# Sumo_main.net
KiCad netlist of a schematic drawn in EAGLE
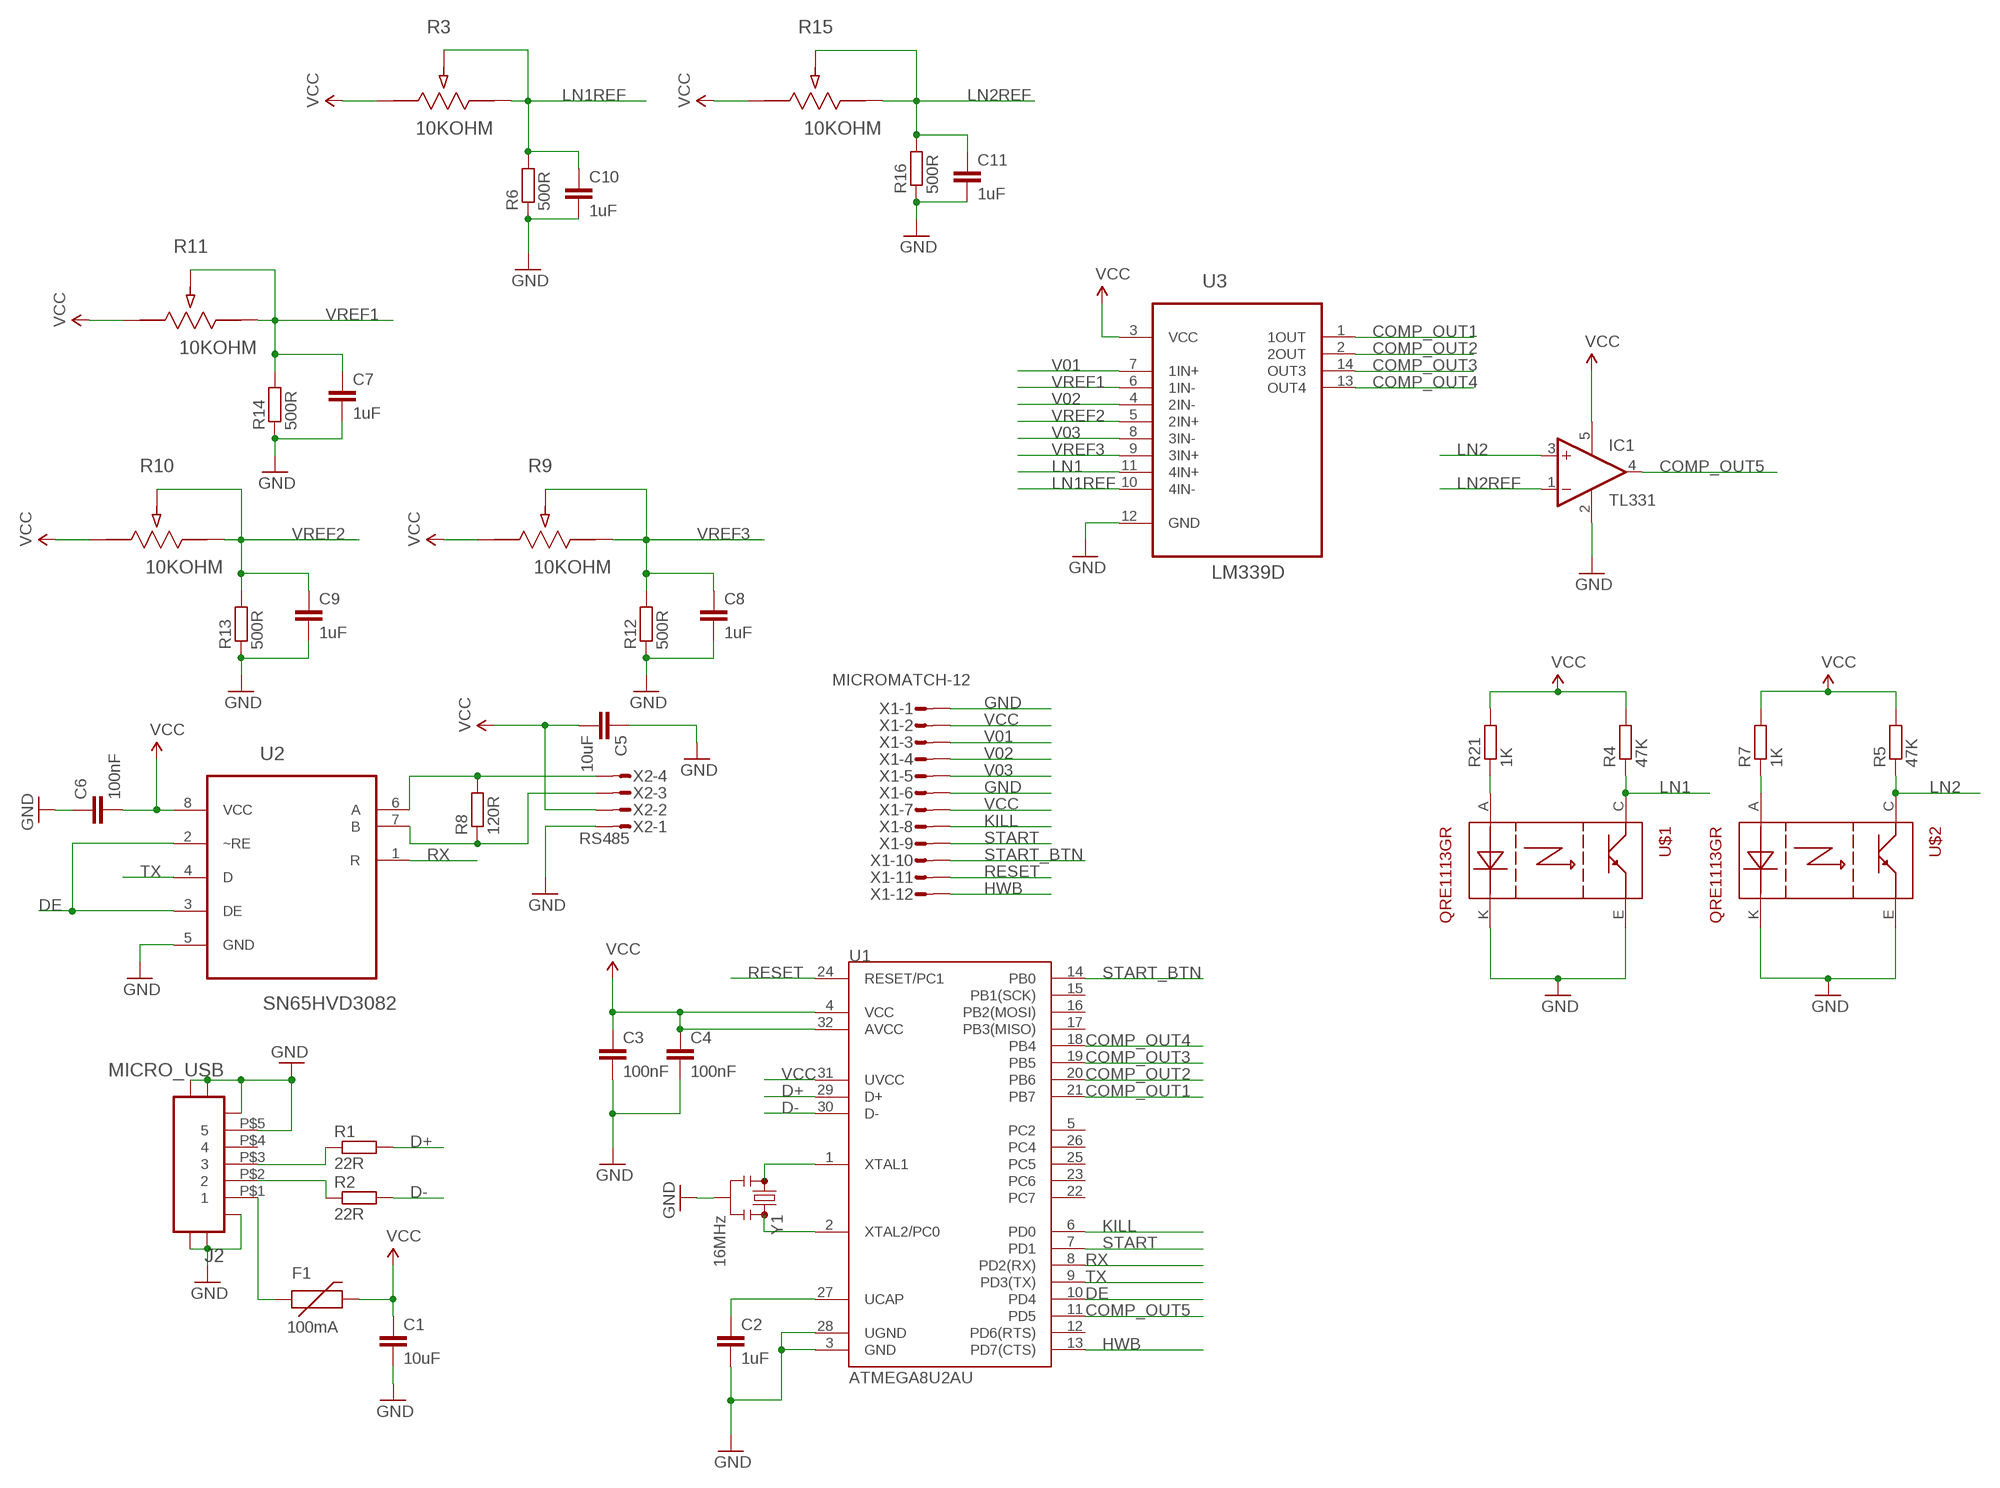
[diagram p0: schematic, sheet 1]

(export (version "E")
  (design (tool "Eeschema 10.0.6"))
  (components
    (comp (ref "C1")
      (value "10uF")
      (footprint "eagle-import:0603-CAP")
      (libsource (lib "eagle-import") (part "CAP0603-CAP"))
    )
    (comp (ref "C2")
      (value "1uF")
      (footprint "eagle-import:0603-CAP")
      (libsource (lib "eagle-import") (part "CAP0603-CAP"))
    )
    (comp (ref "C3")
      (value "100nF")
      (footprint "eagle-import:0603-CAP")
      (libsource (lib "eagle-import") (part "CAP0603-CAP"))
    )
    (comp (ref "C4")
      (value "100nF")
      (footprint "eagle-import:0603-CAP")
      (libsource (lib "eagle-import") (part "CAP0603-CAP"))
    )
    (comp (ref "C5")
      (value "10uF")
      (footprint "eagle-import:0603-CAP")
      (libsource (lib "eagle-import") (part "CAP0603-CAP"))
    )
    (comp (ref "C6")
      (value "100nF")
      (footprint "eagle-import:0603-CAP")
      (libsource (lib "eagle-import") (part "CAP0603-CAP"))
    )
    (comp (ref "C7")
      (value "1uF")
      (footprint "eagle-import:0603-CAP")
      (libsource (lib "eagle-import") (part "CAP0603-CAP"))
    )
    (comp (ref "C8")
      (value "1uF")
      (footprint "eagle-import:0603-CAP")
      (libsource (lib "eagle-import") (part "CAP0603-CAP"))
    )
    (comp (ref "C9")
      (value "1uF")
      (footprint "eagle-import:0603-CAP")
      (libsource (lib "eagle-import") (part "CAP0603-CAP"))
    )
    (comp (ref "C10")
      (value "1uF")
      (footprint "eagle-import:0603-CAP")
      (libsource (lib "eagle-import") (part "CAP0603-CAP"))
    )
    (comp (ref "C11")
      (value "1uF")
      (footprint "eagle-import:0603-CAP")
      (libsource (lib "eagle-import") (part "CAP0603-CAP"))
    )
    (comp (ref "F1")
      (value "100mA")
      (footprint "eagle-import:PTC-1206")
      (libsource (lib "eagle-import") (part "PTCSMD"))
    )
    (comp (ref "IC1")
      (value "TL331")
      (footprint "eagle-import:DBV-R-PDSO-G5")
      (libsource (lib "eagle-import") (part "TL331"))
    )
    (comp (ref "J2")
      (value "MICRO_USB")
      (footprint "eagle-import:MOLEX_47346-0001")
      (fields (field (name "MPN") "47346-0001"))
      (libsource (lib "eagle-import") (part "47346-0001"))
    )
    (comp (ref "R1")
      (value "22R")
      (footprint "eagle-import:R0603")
      (libsource (lib "eagle-import") (part "R-EU_R0603"))
    )
    (comp (ref "R2")
      (value "22R")
      (footprint "eagle-import:R0603")
      (libsource (lib "eagle-import") (part "R-EU_R0603"))
    )
    (comp (ref "R3")
      (value "10KOHM")
      (footprint "eagle-import:POT_EVM3W")
      (fields (field (name "MPN") "EVM3YSX50B14") (field (name "TOLERANCE") "±25 %"))
      (libsource (lib "eagle-import") (part "EVM-3W3YSX50B14"))
    )
    (comp (ref "R4")
      (value "47K")
      (footprint "eagle-import:R0603")
      (libsource (lib "eagle-import") (part "R-EU_R0603"))
    )
    (comp (ref "R5")
      (value "47K")
      (footprint "eagle-import:R0603")
      (libsource (lib "eagle-import") (part "R-EU_R0603"))
    )
    (comp (ref "R6")
      (value "500R")
      (footprint "eagle-import:R0603")
      (libsource (lib "eagle-import") (part "R-EU_R0603"))
    )
    (comp (ref "R7")
      (value "1K")
      (footprint "eagle-import:R0603")
      (libsource (lib "eagle-import") (part "R-EU_R0603"))
    )
    (comp (ref "R8")
      (value "120R")
      (footprint "eagle-import:R0603")
      (libsource (lib "eagle-import") (part "R-EU_R0603"))
    )
    (comp (ref "R9")
      (value "10KOHM")
      (footprint "eagle-import:POT_EVM3W")
      (fields (field (name "MPN") "EVM3YSX50B14") (field (name "TOLERANCE") "±25 %"))
      (libsource (lib "eagle-import") (part "EVM-3W3YSX50B14"))
    )
    (comp (ref "R10")
      (value "10KOHM")
      (footprint "eagle-import:POT_EVM3W")
      (fields (field (name "MPN") "EVM3YSX50B14") (field (name "TOLERANCE") "±25 %"))
      (libsource (lib "eagle-import") (part "EVM-3W3YSX50B14"))
    )
    (comp (ref "R11")
      (value "10KOHM")
      (footprint "eagle-import:POT_EVM3W")
      (fields (field (name "MPN") "EVM3YSX50B14") (field (name "TOLERANCE") "±25 %"))
      (libsource (lib "eagle-import") (part "EVM-3W3YSX50B14"))
    )
    (comp (ref "R12")
      (value "500R")
      (footprint "eagle-import:R0603")
      (libsource (lib "eagle-import") (part "R-EU_R0603"))
    )
    (comp (ref "R13")
      (value "500R")
      (footprint "eagle-import:R0603")
      (libsource (lib "eagle-import") (part "R-EU_R0603"))
    )
    (comp (ref "R14")
      (value "500R")
      (footprint "eagle-import:R0603")
      (libsource (lib "eagle-import") (part "R-EU_R0603"))
    )
    (comp (ref "R15")
      (value "10KOHM")
      (footprint "eagle-import:POT_EVM3W")
      (fields (field (name "MPN") "EVM3YSX50B14") (field (name "TOLERANCE") "±25 %"))
      (libsource (lib "eagle-import") (part "EVM-3W3YSX50B14"))
    )
    (comp (ref "R16")
      (value "500R")
      (footprint "eagle-import:R0603")
      (libsource (lib "eagle-import") (part "R-EU_R0603"))
    )
    (comp (ref "R21")
      (value "1K")
      (footprint "eagle-import:R0603")
      (libsource (lib "eagle-import") (part "R-EU_R0603"))
    )
    (comp (ref "U$1")
      (value "QRE1113GR")
      (footprint "eagle-import:4LEADSMD")
      (libsource (lib "eagle-import") (part "QRE1113GR"))
    )
    (comp (ref "U$2")
      (value "QRE1113GR")
      (footprint "eagle-import:4LEADSMD")
      (libsource (lib "eagle-import") (part "QRE1113GR"))
    )
    (comp (ref "U1")
      (value "ATMEGA8U2AU")
      (footprint "eagle-import:TQFP32-08")
      (libsource (lib "eagle-import") (part "ATMEGA8U2AU"))
    )
    (comp (ref "U2")
      (value "SN65HVD3082")
      (footprint "eagle-import:SOIC127P600X175-8N")
      (fields (field (name "MPN") "SN65HVD3082ED"))
      (libsource (lib "eagle-import") (part "SN65HVD3082ED"))
    )
    (comp (ref "U3")
      (value "LM339D")
      (footprint "eagle-import:SOIC127P600X175-14N")
      (libsource (lib "eagle-import") (part "LM339D"))
    )
    (comp (ref "X1")
      (value "MICROMATCH-12")
      (footprint "eagle-import:MICROMATCH-12")
      (fields (field (name "MF") "FARNELL") (field (name "MPN") "8-215464-2"))
      (libsource (lib "eagle-import") (part "MICROMATCH-12"))
    )
    (comp (ref "X2")
      (value "RS485")
      (footprint "eagle-import:MICROMATCH-4")
      (fields (field (name "MPN") "7-215464-4"))
      (libsource (lib "eagle-import") (part "MICROMATCH-4"))
    )
    (comp (ref "Y1")
      (value "16MHz")
      (footprint "eagle-import:RESONATOR-SMD_MED")
      (libsource (lib "eagle-import") (part "RESONATOR4MHZ"))
    )
  )
  (nets
    (net (code "1") (name "/COMP_OUT1") (class "Default")
      (node (ref "U1") (pin "21") (pinfunction "PB7_21") (pintype "bidirectional"))
      (node (ref "U3") (pin "1") (pinfunction "1OUT_1") (pintype "output"))
    )
    (net (code "2") (name "/COMP_OUT2") (class "Default")
      (node (ref "U1") (pin "20") (pinfunction "PB6_20") (pintype "bidirectional"))
      (node (ref "U3") (pin "2") (pinfunction "2OUT_2") (pintype "output"))
    )
    (net (code "3") (name "/COMP_OUT3") (class "Default")
      (node (ref "U1") (pin "19") (pinfunction "PB5_19") (pintype "bidirectional"))
      (node (ref "U3") (pin "14") (pinfunction "OUT3_14") (pintype "output"))
    )
    (net (code "4") (name "/COMP_OUT4") (class "Default")
      (node (ref "U1") (pin "18") (pinfunction "PB4_18") (pintype "bidirectional"))
      (node (ref "U3") (pin "13") (pinfunction "OUT4_13") (pintype "output"))
    )
    (net (code "5") (name "/COMP_OUT5") (class "Default")
      (node (ref "IC1") (pin "4") (pinfunction "OUT_4") (pintype "output"))
      (node (ref "U1") (pin "11") (pinfunction "PD5_11") (pintype "bidirectional"))
    )
    (net (code "6") (name "/D+") (class "Default")
      (node (ref "R1") (pin "2") (pinfunction "2_2") (pintype "passive"))
      (node (ref "U1") (pin "29") (pinfunction "D+_29") (pintype "bidirectional"))
    )
    (net (code "7") (name "/D-") (class "Default")
      (node (ref "R2") (pin "2") (pinfunction "2_2") (pintype "passive"))
      (node (ref "U1") (pin "30") (pinfunction "D-_30") (pintype "bidirectional"))
    )
    (net (code "8") (name "/DE") (class "Default")
      (node (ref "U1") (pin "10") (pinfunction "PD4_10") (pintype "bidirectional"))
      (node (ref "U2") (pin "2") (pinfunction "~{RE}_2") (pintype "input"))
      (node (ref "U2") (pin "3") (pinfunction "DE_3") (pintype "input"))
    )
    (net (code "9") (name "/HWB") (class "Default")
      (node (ref "U1") (pin "13") (pinfunction "PD7(CTS)_13") (pintype "bidirectional"))
      (node (ref "X1") (pin "12") (pinfunction "S_12") (pintype "passive"))
    )
    (net (code "10") (name "/KILL") (class "Default")
      (node (ref "U1") (pin "6") (pinfunction "PD0_6") (pintype "bidirectional"))
      (node (ref "X1") (pin "8") (pinfunction "S_8") (pintype "passive"))
    )
    (net (code "11") (name "/LN1") (class "Default")
      (node (ref "R4") (pin "1") (pinfunction "1_1") (pintype "passive"))
      (node (ref "U$1") (pin "C") (pinfunction "C_C") (pintype "bidirectional"))
      (node (ref "U3") (pin "11") (pinfunction "4IN+_11") (pintype "input"))
    )
    (net (code "12") (name "/LN1REF") (class "Default")
      (node (ref "C10") (pin "1") (pinfunction "1_1") (pintype "passive"))
      (node (ref "R3") (pin "2") (pinfunction "2_2") (pintype "passive"))
      (node (ref "R3") (pin "3") (pinfunction "3_3") (pintype "passive"))
      (node (ref "R6") (pin "2") (pinfunction "2_2") (pintype "passive"))
      (node (ref "U3") (pin "10") (pinfunction "4IN-_10") (pintype "input"))
    )
    (net (code "13") (name "/LN2") (class "Default")
      (node (ref "IC1") (pin "3") (pinfunction "+IN_3") (pintype "input"))
      (node (ref "R5") (pin "1") (pinfunction "1_1") (pintype "passive"))
      (node (ref "U$2") (pin "C") (pinfunction "C_C") (pintype "bidirectional"))
    )
    (net (code "14") (name "/LN2REF") (class "Default")
      (node (ref "C11") (pin "1") (pinfunction "1_1") (pintype "passive"))
      (node (ref "IC1") (pin "1") (pinfunction "-IN_1") (pintype "input"))
      (node (ref "R15") (pin "2") (pinfunction "2_2") (pintype "passive"))
      (node (ref "R15") (pin "3") (pinfunction "3_3") (pintype "passive"))
      (node (ref "R16") (pin "2") (pinfunction "2_2") (pintype "passive"))
    )
    (net (code "15") (name "/RESET") (class "Default")
      (node (ref "U1") (pin "24") (pinfunction "RESET/PC1_24") (pintype "bidirectional"))
      (node (ref "X1") (pin "11") (pinfunction "S_11") (pintype "passive"))
    )
    (net (code "16") (name "/RX") (class "Default")
      (node (ref "U1") (pin "8") (pinfunction "PD2(RX)_8") (pintype "bidirectional"))
      (node (ref "U2") (pin "1") (pinfunction "R_1") (pintype "output"))
    )
    (net (code "17") (name "/START") (class "Default")
      (node (ref "U1") (pin "7") (pinfunction "PD1_7") (pintype "bidirectional"))
      (node (ref "X1") (pin "9") (pinfunction "S_9") (pintype "passive"))
    )
    (net (code "18") (name "/START_BTN") (class "Default")
      (node (ref "U1") (pin "14") (pinfunction "PB0_14") (pintype "bidirectional"))
      (node (ref "X1") (pin "10") (pinfunction "S_10") (pintype "passive"))
    )
    (net (code "19") (name "/TX") (class "Default")
      (node (ref "U1") (pin "9") (pinfunction "PD3(TX)_9") (pintype "bidirectional"))
      (node (ref "U2") (pin "4") (pinfunction "D_4") (pintype "input"))
    )
    (net (code "20") (name "/V01") (class "Default")
      (node (ref "U3") (pin "7") (pinfunction "1IN+_7") (pintype "input"))
      (node (ref "X1") (pin "3") (pinfunction "S_3") (pintype "passive"))
    )
    (net (code "21") (name "/V02") (class "Default")
      (node (ref "U3") (pin "4") (pinfunction "2IN-_4") (pintype "input"))
      (node (ref "X1") (pin "4") (pinfunction "S_4") (pintype "passive"))
    )
    (net (code "22") (name "/V03") (class "Default")
      (node (ref "U3") (pin "8") (pinfunction "3IN-_8") (pintype "input"))
      (node (ref "X1") (pin "5") (pinfunction "S_5") (pintype "passive"))
    )
    (net (code "23") (name "/VREF1") (class "Default")
      (node (ref "C7") (pin "1") (pinfunction "1_1") (pintype "passive"))
      (node (ref "R11") (pin "2") (pinfunction "2_2") (pintype "passive"))
      (node (ref "R11") (pin "3") (pinfunction "3_3") (pintype "passive"))
      (node (ref "R14") (pin "2") (pinfunction "2_2") (pintype "passive"))
      (node (ref "U3") (pin "6") (pinfunction "1IN-_6") (pintype "input"))
    )
    (net (code "24") (name "/VREF2") (class "Default")
      (node (ref "C9") (pin "1") (pinfunction "1_1") (pintype "passive"))
      (node (ref "R10") (pin "2") (pinfunction "2_2") (pintype "passive"))
      (node (ref "R10") (pin "3") (pinfunction "3_3") (pintype "passive"))
      (node (ref "R13") (pin "2") (pinfunction "2_2") (pintype "passive"))
      (node (ref "U3") (pin "5") (pinfunction "2IN+_5") (pintype "input"))
    )
    (net (code "25") (name "/VREF3") (class "Default")
      (node (ref "C8") (pin "1") (pinfunction "1_1") (pintype "passive"))
      (node (ref "R12") (pin "2") (pinfunction "2_2") (pintype "passive"))
      (node (ref "R9") (pin "2") (pinfunction "2_2") (pintype "passive"))
      (node (ref "R9") (pin "3") (pinfunction "3_3") (pintype "passive"))
      (node (ref "U3") (pin "9") (pinfunction "3IN+_9") (pintype "input"))
    )
    (net (code "26") (name "GND") (class "Default")
      (node (ref "C1") (pin "2") (pinfunction "2_2") (pintype "passive"))
      (node (ref "C10") (pin "2") (pinfunction "2_2") (pintype "passive"))
      (node (ref "C11") (pin "2") (pinfunction "2_2") (pintype "passive"))
      (node (ref "C2") (pin "2") (pinfunction "2_2") (pintype "passive"))
      (node (ref "C3") (pin "2") (pinfunction "2_2") (pintype "passive"))
      (node (ref "C4") (pin "2") (pinfunction "2_2") (pintype "passive"))
      (node (ref "C5") (pin "1") (pinfunction "1_1") (pintype "passive"))
      (node (ref "C6") (pin "1") (pinfunction "1_1") (pintype "passive"))
      (node (ref "C7") (pin "2") (pinfunction "2_2") (pintype "passive"))
      (node (ref "C8") (pin "2") (pinfunction "2_2") (pintype "passive"))
      (node (ref "C9") (pin "2") (pinfunction "2_2") (pintype "passive"))
      (node (ref "IC1") (pin "2") (pinfunction "GND_2") (pintype "power_in"))
      (node (ref "J2") (pin "M1") (pinfunction "P$1_M1") (pintype "bidirectional"))
      (node (ref "J2") (pin "M2") (pinfunction "P$2_M2") (pintype "bidirectional"))
      (node (ref "J2") (pin "M3") (pinfunction "P$3_M3") (pintype "bidirectional"))
      (node (ref "J2") (pin "M4") (pinfunction "P$4_M4") (pintype "bidirectional"))
      (node (ref "J2") (pin "M5") (pinfunction "P$5_M5") (pintype "bidirectional"))
      (node (ref "J2") (pin "M6") (pinfunction "P$6_M6") (pintype "bidirectional"))
      (node (ref "J2") (pin "P$5") (pinfunction "5_P$5") (pintype "input"))
      (node (ref "R12") (pin "1") (pinfunction "1_1") (pintype "passive"))
      (node (ref "R13") (pin "1") (pinfunction "1_1") (pintype "passive"))
      (node (ref "R14") (pin "1") (pinfunction "1_1") (pintype "passive"))
      (node (ref "R16") (pin "1") (pinfunction "1_1") (pintype "passive"))
      (node (ref "R6") (pin "1") (pinfunction "1_1") (pintype "passive"))
      (node (ref "U$1") (pin "E") (pinfunction "E_E") (pintype "bidirectional"))
      (node (ref "U$1") (pin "K") (pinfunction "K_K") (pintype "bidirectional"))
      (node (ref "U$2") (pin "E") (pinfunction "E_E") (pintype "bidirectional"))
      (node (ref "U$2") (pin "K") (pinfunction "K_K") (pintype "bidirectional"))
      (node (ref "U1") (pin "28") (pinfunction "UGND_28") (pintype "bidirectional"))
      (node (ref "U1") (pin "3") (pinfunction "GND_3") (pintype "bidirectional"))
      (node (ref "U2") (pin "5") (pinfunction "GND_5") (pintype "passive"))
      (node (ref "U3") (pin "12") (pinfunction "GND_12") (pintype "passive"))
      (node (ref "X1") (pin "1") (pinfunction "S_1") (pintype "passive"))
      (node (ref "X1") (pin "6") (pinfunction "S_6") (pintype "passive"))
      (node (ref "X2") (pin "1") (pinfunction "S_1") (pintype "passive"))
      (node (ref "Y1") (pin "2") (pinfunction "2_2") (pintype "passive"))
    )
    (net (code "27") (name "Net-(J2-1)") (class "Default")
      (node (ref "F1") (pin "1") (pinfunction "1_1") (pintype "bidirectional"))
      (node (ref "J2") (pin "P$1") (pinfunction "1_P$1") (pintype "input"))
    )
    (net (code "28") (name "Net-(J2-2)") (class "Default")
      (node (ref "J2") (pin "P$2") (pinfunction "2_P$2") (pintype "input"))
      (node (ref "R2") (pin "1") (pinfunction "1_1") (pintype "passive"))
    )
    (net (code "29") (name "Net-(J2-3)") (class "Default")
      (node (ref "J2") (pin "P$3") (pinfunction "3_P$3") (pintype "input"))
      (node (ref "R1") (pin "1") (pinfunction "1_1") (pintype "passive"))
    )
    (net (code "30") (name "Net-(R7-Pad1)") (class "Default")
      (node (ref "R7") (pin "1") (pinfunction "1_1") (pintype "passive"))
      (node (ref "U$2") (pin "A") (pinfunction "A_A") (pintype "bidirectional"))
    )
    (net (code "31") (name "Net-(R21-Pad1)") (class "Default")
      (node (ref "R21") (pin "1") (pinfunction "1_1") (pintype "passive"))
      (node (ref "U$1") (pin "A") (pinfunction "A_A") (pintype "bidirectional"))
    )
    (net (code "32") (name "Net-(U1-UCAP)") (class "Default")
      (node (ref "C2") (pin "1") (pinfunction "1_1") (pintype "passive"))
      (node (ref "U1") (pin "27") (pinfunction "UCAP_27") (pintype "bidirectional"))
    )
    (net (code "33") (name "Net-(U1-XTAL1)") (class "Default")
      (node (ref "U1") (pin "1") (pinfunction "XTAL1_1") (pintype "bidirectional"))
      (node (ref "Y1") (pin "1") (pinfunction "1_1") (pintype "passive"))
    )
    (net (code "34") (name "Net-(U1-XTAL2{slash}PC0)") (class "Default")
      (node (ref "U1") (pin "2") (pinfunction "XTAL2/PC0_2") (pintype "bidirectional"))
      (node (ref "Y1") (pin "3") (pinfunction "3_3") (pintype "passive"))
    )
    (net (code "35") (name "Net-(U2-A)") (class "Default")
      (node (ref "R8") (pin "2") (pinfunction "2_2") (pintype "passive"))
      (node (ref "U2") (pin "6") (pinfunction "A_6") (pintype "output"))
      (node (ref "X2") (pin "4") (pinfunction "S_4") (pintype "passive"))
    )
    (net (code "36") (name "Net-(U2-B)") (class "Default")
      (node (ref "R8") (pin "1") (pinfunction "1_1") (pintype "passive"))
      (node (ref "U2") (pin "7") (pinfunction "B_7") (pintype "output"))
      (node (ref "X2") (pin "3") (pinfunction "S_3") (pintype "passive"))
    )
    (net (code "37") (name "VCC") (class "Default")
      (node (ref "C1") (pin "1") (pinfunction "1_1") (pintype "passive"))
      (node (ref "C3") (pin "1") (pinfunction "1_1") (pintype "passive"))
      (node (ref "C4") (pin "1") (pinfunction "1_1") (pintype "passive"))
      (node (ref "C5") (pin "2") (pinfunction "2_2") (pintype "passive"))
      (node (ref "C6") (pin "2") (pinfunction "2_2") (pintype "passive"))
      (node (ref "F1") (pin "2") (pinfunction "2_2") (pintype "bidirectional"))
      (node (ref "IC1") (pin "5") (pinfunction "V+_5") (pintype "power_in"))
      (node (ref "R10") (pin "1") (pinfunction "1_1") (pintype "passive"))
      (node (ref "R11") (pin "1") (pinfunction "1_1") (pintype "passive"))
      (node (ref "R15") (pin "1") (pinfunction "1_1") (pintype "passive"))
      (node (ref "R21") (pin "2") (pinfunction "2_2") (pintype "passive"))
      (node (ref "R3") (pin "1") (pinfunction "1_1") (pintype "passive"))
      (node (ref "R4") (pin "2") (pinfunction "2_2") (pintype "passive"))
      (node (ref "R5") (pin "2") (pinfunction "2_2") (pintype "passive"))
      (node (ref "R7") (pin "2") (pinfunction "2_2") (pintype "passive"))
      (node (ref "R9") (pin "1") (pinfunction "1_1") (pintype "passive"))
      (node (ref "U1") (pin "31") (pinfunction "UVCC_31") (pintype "bidirectional"))
      (node (ref "U1") (pin "32") (pinfunction "AVCC_32") (pintype "bidirectional"))
      (node (ref "U1") (pin "4") (pinfunction "VCC_4") (pintype "bidirectional"))
      (node (ref "U2") (pin "8") (pinfunction "VCC_8") (pintype "power_in"))
      (node (ref "U3") (pin "3") (pinfunction "VCC_3") (pintype "power_in"))
      (node (ref "X1") (pin "2") (pinfunction "S_2") (pintype "passive"))
      (node (ref "X1") (pin "7") (pinfunction "S_7") (pintype "passive"))
      (node (ref "X2") (pin "2") (pinfunction "S_2") (pintype "passive"))
    )
    (net (code "38") (name "unconnected-(J2-4-PadP$4)") (class "Default")
      (node (ref "J2") (pin "P$4") (pinfunction "4_P$4") (pintype "input"))
    )
    (net (code "39") (name "unconnected-(U1-PB1(SCK)-Pad15)") (class "Default")
      (node (ref "U1") (pin "15") (pinfunction "PB1(SCK)_15") (pintype "bidirectional"))
    )
    (net (code "40") (name "unconnected-(U1-PB2(MOSI)-Pad16)") (class "Default")
      (node (ref "U1") (pin "16") (pinfunction "PB2(MOSI)_16") (pintype "bidirectional"))
    )
    (net (code "41") (name "unconnected-(U1-PB3(MISO)-Pad17)") (class "Default")
      (node (ref "U1") (pin "17") (pinfunction "PB3(MISO)_17") (pintype "bidirectional"))
    )
    (net (code "42") (name "unconnected-(U1-PC2-Pad5)") (class "Default")
      (node (ref "U1") (pin "5") (pinfunction "PC2_5") (pintype "bidirectional"))
    )
    (net (code "43") (name "unconnected-(U1-PC4-Pad26)") (class "Default")
      (node (ref "U1") (pin "26") (pinfunction "PC4_26") (pintype "bidirectional"))
    )
    (net (code "44") (name "unconnected-(U1-PC5-Pad25)") (class "Default")
      (node (ref "U1") (pin "25") (pinfunction "PC5_25") (pintype "bidirectional"))
    )
    (net (code "45") (name "unconnected-(U1-PC6-Pad23)") (class "Default")
      (node (ref "U1") (pin "23") (pinfunction "PC6_23") (pintype "bidirectional"))
    )
    (net (code "46") (name "unconnected-(U1-PC7-Pad22)") (class "Default")
      (node (ref "U1") (pin "22") (pinfunction "PC7_22") (pintype "bidirectional"))
    )
    (net (code "47") (name "unconnected-(U1-PD6(RTS)-Pad12)") (class "Default")
      (node (ref "U1") (pin "12") (pinfunction "PD6(RTS)_12") (pintype "bidirectional"))
    )
  )
)
